# uno.net
KiCad netlist of a schematic drawn in EAGLE
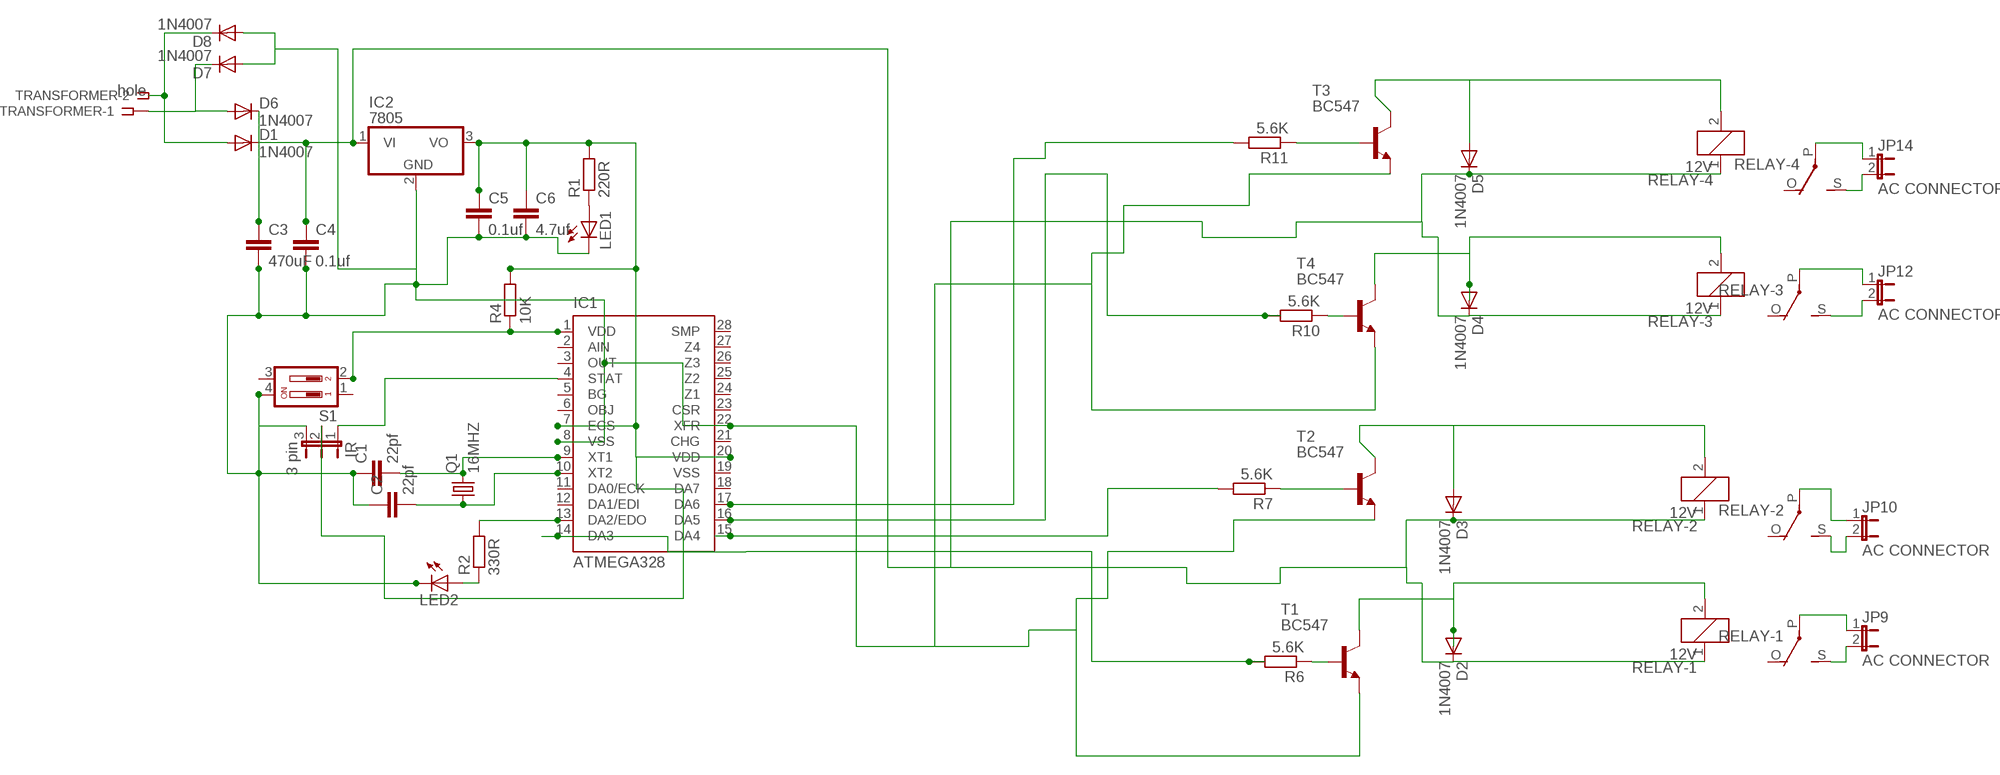
[diagram p0: schematic, sheet 1]

(export (version "E")
  (design (tool "Eeschema 10.0.6"))
  (components
    (comp (ref "C1")
      (value "22pf")
      (footprint "eagle-import:C2.5-2")
      (libsource (lib "eagle-import") (part "C2.5/2"))
    )
    (comp (ref "C2")
      (value "22pf")
      (footprint "eagle-import:C2.5-2")
      (libsource (lib "eagle-import") (part "C2.5/2"))
    )
    (comp (ref "C3")
      (value "470uF")
      (footprint "eagle-import:C2.5-2")
      (libsource (lib "eagle-import") (part "C2.5/2"))
    )
    (comp (ref "C4")
      (value "0.1uf")
      (footprint "eagle-import:C2.5-2")
      (libsource (lib "eagle-import") (part "C2.5/2"))
    )
    (comp (ref "C5")
      (value "0.1uf")
      (footprint "eagle-import:C2.5-2")
      (libsource (lib "eagle-import") (part "C2.5/2"))
    )
    (comp (ref "C6")
      (value "4.7uf")
      (footprint "eagle-import:C2.5-2")
      (libsource (lib "eagle-import") (part "C2.5/2"))
    )
    (comp (ref "D1")
      (value "1N4007")
      (footprint "eagle-import:DO41-10")
      (libsource (lib "eagle-import") (part "1N4004"))
    )
    (comp (ref "D2")
      (value "1N4007")
      (footprint "eagle-import:DO41-10")
      (libsource (lib "eagle-import") (part "1N4004"))
    )
    (comp (ref "D3")
      (value "1N4007")
      (footprint "eagle-import:DO41-10")
      (libsource (lib "eagle-import") (part "1N4004"))
    )
    (comp (ref "D4")
      (value "1N4007")
      (footprint "eagle-import:DO41-10")
      (libsource (lib "eagle-import") (part "1N4004"))
    )
    (comp (ref "D5")
      (value "1N4007")
      (footprint "eagle-import:DO41-10")
      (libsource (lib "eagle-import") (part "1N4004"))
    )
    (comp (ref "D6")
      (value "1N4007")
      (footprint "eagle-import:DO41-10")
      (libsource (lib "eagle-import") (part "1N4004"))
    )
    (comp (ref "D7")
      (value "1N4007")
      (footprint "eagle-import:DO41-10")
      (libsource (lib "eagle-import") (part "1N4004"))
    )
    (comp (ref "D8")
      (value "1N4007")
      (footprint "eagle-import:DO41-10")
      (libsource (lib "eagle-import") (part "1N4004"))
    )
    (comp (ref "IC1")
      (value "ATMEGA328")
      (footprint "eagle-import:DIL28-3")
      (libsource (lib "eagle-import") (part "QT9701BD"))
    )
    (comp (ref "IC2")
      (value "7805")
      (footprint "eagle-import:TO220V")
      (libsource (lib "eagle-import") (part "78TV6"))
    )
    (comp (ref "IR")
      (value "3 pin")
      (footprint "eagle-import:JP2")
      (libsource (lib "eagle-import") (part "JP2E"))
    )
    (comp (ref "JP9")
      (value "AC CONNECTOR")
      (footprint "eagle-import:JP1")
      (libsource (lib "eagle-import") (part "JP1E"))
    )
    (comp (ref "JP10")
      (value "AC CONNECTOR")
      (footprint "eagle-import:JP1")
      (libsource (lib "eagle-import") (part "JP1E"))
    )
    (comp (ref "JP12")
      (value "AC CONNECTOR")
      (footprint "eagle-import:JP1")
      (libsource (lib "eagle-import") (part "JP1E"))
    )
    (comp (ref "JP14")
      (value "AC CONNECTOR")
      (footprint "eagle-import:JP1")
      (libsource (lib "eagle-import") (part "JP1E"))
    )
    (comp (ref "LED1")
      (value "LED3MM")
      (footprint "eagle-import:LED3MM")
      (libsource (lib "eagle-import") (part "LED3MM"))
    )
    (comp (ref "LED2")
      (value "LED3MM")
      (footprint "eagle-import:LED3MM")
      (libsource (lib "eagle-import") (part "LED3MM"))
    )
    (comp (ref "Q1")
      (value "16MHZ")
      (footprint "eagle-import:HC49_S")
      (libsource (lib "eagle-import") (part "CRYSTALHC49S"))
    )
    (comp (ref "R1")
      (value "220R")
      (footprint "eagle-import:0207_10")
      (libsource (lib "eagle-import") (part "R-EU_0207/10"))
    )
    (comp (ref "R2")
      (value "330R")
      (footprint "eagle-import:0207_10")
      (libsource (lib "eagle-import") (part "R-EU_0207/10"))
    )
    (comp (ref "R4")
      (value "10K")
      (footprint "eagle-import:0207_10")
      (libsource (lib "eagle-import") (part "R-EU_0207/10"))
    )
    (comp (ref "R6")
      (value "5.6K")
      (footprint "eagle-import:0204_7")
      (libsource (lib "eagle-import") (part "R-EU_0204/7"))
    )
    (comp (ref "R7")
      (value "5.6K")
      (footprint "eagle-import:0204_7")
      (libsource (lib "eagle-import") (part "R-EU_0204/7"))
    )
    (comp (ref "R10")
      (value "5.6K")
      (footprint "eagle-import:0204_7")
      (libsource (lib "eagle-import") (part "R-EU_0204/7"))
    )
    (comp (ref "R11")
      (value "5.6K")
      (footprint "eagle-import:0204_7")
      (libsource (lib "eagle-import") (part "R-EU_0204/7"))
    )
    (comp (ref "RELAY-1")
      (value "12V")
      (footprint "eagle-import:G5LE")
      (libsource (lib "eagle-import") (part "G5L"))
    )
    (comp (ref "RELAY-2")
      (value "12V")
      (footprint "eagle-import:G5LE")
      (libsource (lib "eagle-import") (part "G5L"))
    )
    (comp (ref "RELAY-3")
      (value "12V")
      (footprint "eagle-import:G5LE")
      (libsource (lib "eagle-import") (part "G5L"))
    )
    (comp (ref "RELAY-4")
      (value "12V")
      (footprint "eagle-import:G5LE")
      (libsource (lib "eagle-import") (part "G5L"))
    )
    (comp (ref "S1")
      (value "DP02")
      (footprint "eagle-import:DP-02")
      (fields (field (name "MPN") "MCDP02"))
      (libsource (lib "eagle-import") (part "DP02"))
    )
    (comp (ref "T1")
      (value "BC547")
      (footprint "eagle-import:TO92")
      (libsource (lib "eagle-import") (part "BC547"))
    )
    (comp (ref "T2")
      (value "BC547")
      (footprint "eagle-import:TO92")
      (libsource (lib "eagle-import") (part "BC547"))
    )
    (comp (ref "T3")
      (value "BC547")
      (footprint "eagle-import:TO92")
      (libsource (lib "eagle-import") (part "BC547"))
    )
    (comp (ref "T4")
      (value "BC547")
      (footprint "eagle-import:TO92")
      (libsource (lib "eagle-import") (part "BC547"))
    )
    (comp (ref "TRANSFORMER")
      (value "hole")
      (footprint "eagle-import:SSW-101-02-S-D")
      (fields (field (name "MPN") "SSW-101-02-S-D"))
      (libsource (lib "eagle-import") (part "SSW-101-02-S-D"))
    )
  )
  (nets
    (net (code "1") (name "Net-(D6-PadA)") (class "Default")
      (node (ref "D6") (pin "A") (pinfunction "A_A") (pintype "passive"))
      (node (ref "D7") (pin "C") (pinfunction "C_C") (pintype "passive"))
      (node (ref "TRANSFORMER") (pin "1") (pinfunction "1_1") (pintype "passive"))
    )
    (net (code "2") (name "Net-(IC1-DA2{slash}EDO)") (class "Default")
      (node (ref "IC1") (pin "13") (pinfunction "DA2/EDO_13") (pintype "output"))
      (node (ref "R2") (pin "2") (pinfunction "2_2") (pintype "passive"))
    )
    (net (code "3") (name "Net-(IC1-DA3)") (class "Default")
      (node (ref "IC1") (pin "14") (pinfunction "DA3_14") (pintype "output"))
      (node (ref "R6") (pin "2") (pinfunction "2_2") (pintype "passive"))
    )
    (net (code "4") (name "Net-(IC1-DA4)") (class "Default")
      (node (ref "IC1") (pin "15") (pinfunction "DA4_15") (pintype "output"))
      (node (ref "R7") (pin "2") (pinfunction "2_2") (pintype "passive"))
    )
    (net (code "5") (name "Net-(IC1-DA5)") (class "Default")
      (node (ref "IC1") (pin "16") (pinfunction "DA5_16") (pintype "output"))
      (node (ref "R10") (pin "2") (pinfunction "2_2") (pintype "passive"))
    )
    (net (code "6") (name "Net-(IC1-DA6)") (class "Default")
      (node (ref "IC1") (pin "17") (pinfunction "DA6_17") (pintype "output"))
      (node (ref "R11") (pin "2") (pinfunction "2_2") (pintype "passive"))
    )
    (net (code "7") (name "Net-(IC1-ECS)") (class "Default")
      (node (ref "C5") (pin "1") (pinfunction "1_1") (pintype "passive"))
      (node (ref "C6") (pin "1") (pinfunction "1_1") (pintype "passive"))
      (node (ref "IC1") (pin "20") (pinfunction "VDD_20") (pintype "input"))
      (node (ref "IC1") (pin "7") (pinfunction "ECS_7") (pintype "output"))
      (node (ref "IC2") (pin "3") (pinfunction "VO_3") (pintype "passive"))
      (node (ref "IR") (pin "2") (pinfunction "2_2") (pintype "passive"))
      (node (ref "R1") (pin "2") (pinfunction "2_2") (pintype "passive"))
      (node (ref "R4") (pin "2") (pinfunction "2_2") (pintype "passive"))
    )
    (net (code "8") (name "Net-(IC1-STAT)") (class "Default")
      (node (ref "IC1") (pin "4") (pinfunction "STAT_4") (pintype "output"))
      (node (ref "IR") (pin "1") (pinfunction "1_1") (pintype "passive"))
    )
    (net (code "9") (name "Net-(IC1-VDD-Pad1)") (class "Default")
      (node (ref "IC1") (pin "1") (pinfunction "VDD_1") (pintype "input"))
      (node (ref "R4") (pin "1") (pinfunction "1_1") (pintype "passive"))
      (node (ref "S1") (pin "2") (pinfunction "2_2") (pintype "passive"))
    )
    (net (code "10") (name "Net-(IC1-XFR)") (class "Default")
      (node (ref "C1") (pin "1") (pinfunction "1_1") (pintype "passive"))
      (node (ref "C2") (pin "1") (pinfunction "1_1") (pintype "passive"))
      (node (ref "C3") (pin "2") (pinfunction "2_2") (pintype "passive"))
      (node (ref "C4") (pin "2") (pinfunction "2_2") (pintype "passive"))
      (node (ref "C5") (pin "2") (pinfunction "2_2") (pintype "passive"))
      (node (ref "C6") (pin "2") (pinfunction "2_2") (pintype "passive"))
      (node (ref "D7") (pin "A") (pinfunction "A_A") (pintype "passive"))
      (node (ref "D8") (pin "A") (pinfunction "A_A") (pintype "passive"))
      (node (ref "IC1") (pin "22") (pinfunction "XFR_22") (pintype "output"))
      (node (ref "IC1") (pin "8") (pinfunction "VSS_8") (pintype "input"))
      (node (ref "IC2") (pin "2") (pinfunction "GND_2") (pintype "passive"))
      (node (ref "IR") (pin "3") (pinfunction "3_3") (pintype "passive"))
      (node (ref "LED1") (pin "K") (pinfunction "C_K") (pintype "passive"))
      (node (ref "LED2") (pin "K") (pinfunction "C_K") (pintype "passive"))
      (node (ref "S1") (pin "4") (pinfunction "4_4") (pintype "passive"))
      (node (ref "T1") (pin "1") (pinfunction "E_1") (pintype "passive"))
      (node (ref "T2") (pin "1") (pinfunction "E_1") (pintype "passive"))
      (node (ref "T3") (pin "1") (pinfunction "E_1") (pintype "passive"))
      (node (ref "T4") (pin "1") (pinfunction "E_1") (pintype "passive"))
    )
    (net (code "11") (name "Net-(IC1-XT1)") (class "Default")
      (node (ref "C1") (pin "2") (pinfunction "2_2") (pintype "passive"))
      (node (ref "IC1") (pin "9") (pinfunction "XT1_9") (pintype "input"))
      (node (ref "Q1") (pin "2") (pinfunction "2_2") (pintype "passive"))
    )
    (net (code "12") (name "Net-(IC1-XT2)") (class "Default")
      (node (ref "C2") (pin "2") (pinfunction "2_2") (pintype "passive"))
      (node (ref "IC1") (pin "10") (pinfunction "XT2_10") (pintype "output"))
      (node (ref "Q1") (pin "1") (pinfunction "1_1") (pintype "passive"))
    )
    (net (code "13") (name "Net-(IC2-VI)") (class "Default")
      (node (ref "C3") (pin "1") (pinfunction "1_1") (pintype "passive"))
      (node (ref "C4") (pin "1") (pinfunction "1_1") (pintype "passive"))
      (node (ref "D1") (pin "C") (pinfunction "C_C") (pintype "passive"))
      (node (ref "D2") (pin "C") (pinfunction "C_C") (pintype "passive"))
      (node (ref "D3") (pin "C") (pinfunction "C_C") (pintype "passive"))
      (node (ref "D4") (pin "C") (pinfunction "C_C") (pintype "passive"))
      (node (ref "D5") (pin "C") (pinfunction "C_C") (pintype "passive"))
      (node (ref "D6") (pin "C") (pinfunction "C_C") (pintype "passive"))
      (node (ref "IC2") (pin "1") (pinfunction "VI_1") (pintype "input"))
      (node (ref "RELAY-1") (pin "1") (pinfunction "1_1") (pintype "passive"))
      (node (ref "RELAY-2") (pin "1") (pinfunction "1_1") (pintype "passive"))
      (node (ref "RELAY-3") (pin "1") (pinfunction "1_1") (pintype "passive"))
      (node (ref "RELAY-4") (pin "1") (pinfunction "1_1") (pintype "passive"))
    )
    (net (code "14") (name "Net-(JP9-Pad1)") (class "Default")
      (node (ref "JP9") (pin "1") (pinfunction "1_1") (pintype "passive"))
      (node (ref "RELAY-1") (pin "P") (pinfunction "P_P") (pintype "passive"))
    )
    (net (code "15") (name "Net-(JP9-Pad2)") (class "Default")
      (node (ref "JP9") (pin "2") (pinfunction "2_2") (pintype "passive"))
      (node (ref "RELAY-1") (pin "S") (pinfunction "S_S") (pintype "passive"))
    )
    (net (code "16") (name "Net-(JP10-Pad1)") (class "Default")
      (node (ref "JP10") (pin "1") (pinfunction "1_1") (pintype "passive"))
      (node (ref "RELAY-2") (pin "P") (pinfunction "P_P") (pintype "passive"))
    )
    (net (code "17") (name "Net-(JP10-Pad2)") (class "Default")
      (node (ref "JP10") (pin "2") (pinfunction "2_2") (pintype "passive"))
      (node (ref "RELAY-2") (pin "S") (pinfunction "S_S") (pintype "passive"))
    )
    (net (code "18") (name "Net-(JP12-Pad1)") (class "Default")
      (node (ref "JP12") (pin "1") (pinfunction "1_1") (pintype "passive"))
      (node (ref "RELAY-3") (pin "P") (pinfunction "P_P") (pintype "passive"))
    )
    (net (code "19") (name "Net-(JP12-Pad2)") (class "Default")
      (node (ref "JP12") (pin "2") (pinfunction "2_2") (pintype "passive"))
      (node (ref "RELAY-3") (pin "S") (pinfunction "S_S") (pintype "passive"))
    )
    (net (code "20") (name "Net-(JP14-Pad1)") (class "Default")
      (node (ref "JP14") (pin "1") (pinfunction "1_1") (pintype "passive"))
      (node (ref "RELAY-4") (pin "P") (pinfunction "P_P") (pintype "passive"))
    )
    (net (code "21") (name "Net-(JP14-Pad2)") (class "Default")
      (node (ref "JP14") (pin "2") (pinfunction "2_2") (pintype "passive"))
      (node (ref "RELAY-4") (pin "S") (pinfunction "S_S") (pintype "passive"))
    )
    (net (code "22") (name "Net-(LED1-PadA)") (class "Default")
      (node (ref "LED1") (pin "A") (pinfunction "A_A") (pintype "passive"))
      (node (ref "R1") (pin "1") (pinfunction "1_1") (pintype "passive"))
    )
    (net (code "23") (name "Net-(LED2-PadA)") (class "Default")
      (node (ref "LED2") (pin "A") (pinfunction "A_A") (pintype "passive"))
      (node (ref "R2") (pin "1") (pinfunction "1_1") (pintype "passive"))
    )
    (net (code "24") (name "Net-(T1-B)") (class "Default")
      (node (ref "R6") (pin "1") (pinfunction "1_1") (pintype "passive"))
      (node (ref "T1") (pin "2") (pinfunction "B_2") (pintype "passive"))
    )
    (net (code "25") (name "Net-(T1-C)") (class "Default")
      (node (ref "D2") (pin "A") (pinfunction "A_A") (pintype "passive"))
      (node (ref "RELAY-1") (pin "2") (pinfunction "2_2") (pintype "passive"))
      (node (ref "T1") (pin "3") (pinfunction "C_3") (pintype "passive"))
    )
    (net (code "26") (name "Net-(T2-B)") (class "Default")
      (node (ref "R7") (pin "1") (pinfunction "1_1") (pintype "passive"))
      (node (ref "T2") (pin "2") (pinfunction "B_2") (pintype "passive"))
    )
    (net (code "27") (name "Net-(T2-C)") (class "Default")
      (node (ref "D3") (pin "A") (pinfunction "A_A") (pintype "passive"))
      (node (ref "RELAY-2") (pin "2") (pinfunction "2_2") (pintype "passive"))
      (node (ref "T2") (pin "3") (pinfunction "C_3") (pintype "passive"))
    )
    (net (code "28") (name "Net-(T3-B)") (class "Default")
      (node (ref "R11") (pin "1") (pinfunction "1_1") (pintype "passive"))
      (node (ref "T3") (pin "2") (pinfunction "B_2") (pintype "passive"))
    )
    (net (code "29") (name "Net-(T3-C)") (class "Default")
      (node (ref "D5") (pin "A") (pinfunction "A_A") (pintype "passive"))
      (node (ref "RELAY-4") (pin "2") (pinfunction "2_2") (pintype "passive"))
      (node (ref "T3") (pin "3") (pinfunction "C_3") (pintype "passive"))
    )
    (net (code "30") (name "Net-(T4-B)") (class "Default")
      (node (ref "R10") (pin "1") (pinfunction "1_1") (pintype "passive"))
      (node (ref "T4") (pin "2") (pinfunction "B_2") (pintype "passive"))
    )
    (net (code "31") (name "Net-(T4-C)") (class "Default")
      (node (ref "D4") (pin "A") (pinfunction "A_A") (pintype "passive"))
      (node (ref "RELAY-3") (pin "2") (pinfunction "2_2") (pintype "passive"))
      (node (ref "T4") (pin "3") (pinfunction "C_3") (pintype "passive"))
    )
    (net (code "32") (name "Net-(TRANSFORMERB-1)") (class "Default")
      (node (ref "D1") (pin "A") (pinfunction "A_A") (pintype "passive"))
      (node (ref "D8") (pin "C") (pinfunction "C_C") (pintype "passive"))
      (node (ref "TRANSFORMER") (pin "2") (pinfunction "1_2") (pintype "passive"))
    )
    (net (code "33") (name "unconnected-(IC1-AIN-Pad2)") (class "Default")
      (node (ref "IC1") (pin "2") (pinfunction "AIN_2") (pintype "input"))
    )
    (net (code "34") (name "unconnected-(IC1-BG-Pad5)") (class "Default")
      (node (ref "IC1") (pin "5") (pinfunction "BG_5") (pintype "input"))
    )
    (net (code "35") (name "unconnected-(IC1-CHG-Pad21)") (class "Default")
      (node (ref "IC1") (pin "21") (pinfunction "CHG_21") (pintype "output"))
    )
    (net (code "36") (name "unconnected-(IC1-CSR-Pad23)") (class "Default")
      (node (ref "IC1") (pin "23") (pinfunction "CSR_23") (pintype "output"))
    )
    (net (code "37") (name "unconnected-(IC1-DA0{slash}ECK-Pad11)") (class "Default")
      (node (ref "IC1") (pin "11") (pinfunction "DA0/ECK_11") (pintype "output"))
    )
    (net (code "38") (name "unconnected-(IC1-DA1{slash}EDI-Pad12)") (class "Default")
      (node (ref "IC1") (pin "12") (pinfunction "DA1/EDI_12") (pintype "output"))
    )
    (net (code "39") (name "unconnected-(IC1-DA7-Pad18)") (class "Default")
      (node (ref "IC1") (pin "18") (pinfunction "DA7_18") (pintype "output"))
    )
    (net (code "40") (name "unconnected-(IC1-OBJ-Pad6)") (class "Default")
      (node (ref "IC1") (pin "6") (pinfunction "OBJ_6") (pintype "input"))
    )
    (net (code "41") (name "unconnected-(IC1-OUT-Pad3)") (class "Default")
      (node (ref "IC1") (pin "3") (pinfunction "OUT_3") (pintype "output"))
    )
    (net (code "42") (name "unconnected-(IC1-SMP-Pad28)") (class "Default")
      (node (ref "IC1") (pin "28") (pinfunction "SMP_28") (pintype "output"))
    )
    (net (code "43") (name "unconnected-(IC1-VSS-Pad19)") (class "Default")
      (node (ref "IC1") (pin "19") (pinfunction "VSS_19") (pintype "input"))
    )
    (net (code "44") (name "unconnected-(IC1-Z1-Pad24)") (class "Default")
      (node (ref "IC1") (pin "24") (pinfunction "Z1_24") (pintype "output"))
    )
    (net (code "45") (name "unconnected-(IC1-Z2-Pad25)") (class "Default")
      (node (ref "IC1") (pin "25") (pinfunction "Z2_25") (pintype "output"))
    )
    (net (code "46") (name "unconnected-(IC1-Z3-Pad26)") (class "Default")
      (node (ref "IC1") (pin "26") (pinfunction "Z3_26") (pintype "output"))
    )
    (net (code "47") (name "unconnected-(IC1-Z4-Pad27)") (class "Default")
      (node (ref "IC1") (pin "27") (pinfunction "Z4_27") (pintype "output"))
    )
    (net (code "48") (name "unconnected-(RELAY-1-PadO)") (class "Default")
      (node (ref "RELAY-1") (pin "O") (pinfunction "O_O") (pintype "passive"))
    )
    (net (code "49") (name "unconnected-(RELAY-2-PadO)") (class "Default")
      (node (ref "RELAY-2") (pin "O") (pinfunction "O_O") (pintype "passive"))
    )
    (net (code "50") (name "unconnected-(RELAY-3-PadO)") (class "Default")
      (node (ref "RELAY-3") (pin "O") (pinfunction "O_O") (pintype "passive"))
    )
    (net (code "51") (name "unconnected-(RELAY-4-PadO)") (class "Default")
      (node (ref "RELAY-4") (pin "O") (pinfunction "O_O") (pintype "passive"))
    )
    (net (code "52") (name "unconnected-(S1-Pad1)") (class "Default")
      (node (ref "S1") (pin "1") (pinfunction "1_1") (pintype "passive"))
    )
    (net (code "53") (name "unconnected-(S1-Pad3)") (class "Default")
      (node (ref "S1") (pin "3") (pinfunction "3_3") (pintype "passive"))
    )
  )
)
